# Ga_zkaUk_ad.net
KiCad netlist of a schematic drawn in EAGLE
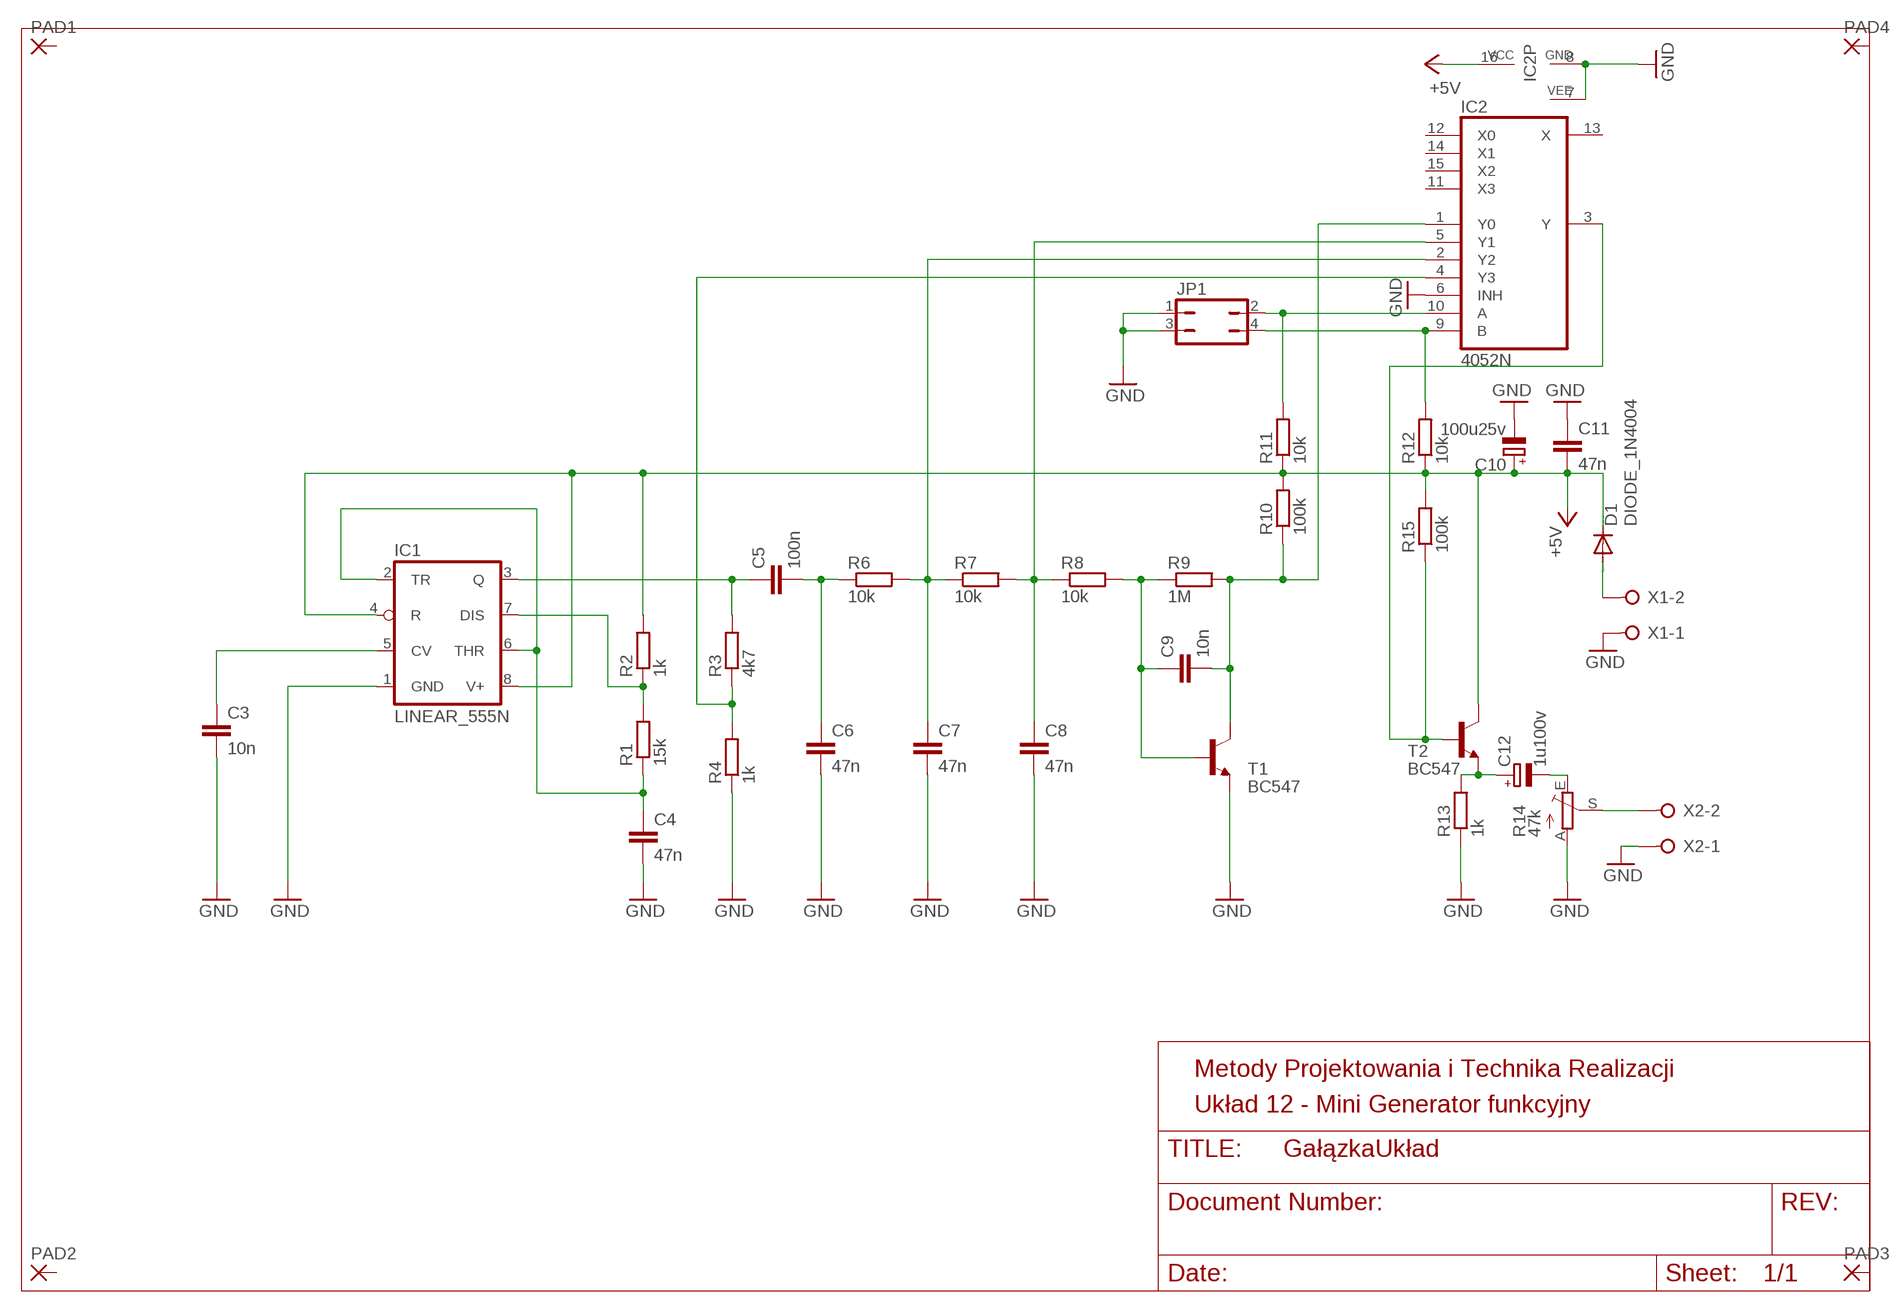
[diagram p0: schematic, sheet 1]

(export (version "E")
  (design (tool "Eeschema 10.0.6"))
  (components
    (comp (ref "C3")
      (value "10n")
      (footprint "eagle-import:C1206")
      (libsource (lib "eagle-import") (part "C-EUC1206"))
    )
    (comp (ref "C4")
      (value "47n")
      (footprint "eagle-import:C1206")
      (libsource (lib "eagle-import") (part "C-EUC1206"))
    )
    (comp (ref "C5")
      (value "100n")
      (footprint "eagle-import:C1206")
      (libsource (lib "eagle-import") (part "C-EUC1206"))
    )
    (comp (ref "C6")
      (value "47n")
      (footprint "eagle-import:C1206")
      (libsource (lib "eagle-import") (part "C-EUC1206"))
    )
    (comp (ref "C7")
      (value "47n")
      (footprint "eagle-import:C1206")
      (libsource (lib "eagle-import") (part "C-EUC1206"))
    )
    (comp (ref "C8")
      (value "47n")
      (footprint "eagle-import:C1206")
      (libsource (lib "eagle-import") (part "C-EUC1206"))
    )
    (comp (ref "C9")
      (value "10n")
      (footprint "eagle-import:C1206")
      (libsource (lib "eagle-import") (part "C-EUC1206"))
    )
    (comp (ref "C10")
      (value "100u25v")
      (footprint "eagle-import:RCL_E2,5-6")
      (libsource (lib "eagle-import") (part "RCL_CPOL-EUE2.5-6"))
    )
    (comp (ref "C11")
      (value "47n")
      (footprint "eagle-import:C1206")
      (libsource (lib "eagle-import") (part "C-EUC1206"))
    )
    (comp (ref "C12")
      (value "1u100v")
      (footprint "eagle-import:E2-5")
      (libsource (lib "eagle-import") (part "CPOL-EUE2-5"))
    )
    (comp (ref "D1")
      (value "DIODE_1N4004")
      (footprint "eagle-import:DIODE_DO41-10")
      (libsource (lib "eagle-import") (part "DIODE_1N4004"))
    )
    (comp (ref "IC1")
      (value "LINEAR_555N")
      (footprint "eagle-import:LINEAR_DIL08")
      (libsource (lib "eagle-import") (part "LINEAR_555N"))
    )
    (comp (ref "IC2")
      (value "4052N")
      (footprint "eagle-import:DIL16")
      (libsource (lib "eagle-import") (part "4052N"))
    )
    (comp (ref "JP1")
      (value "JUMPER_JP2Q")
      (footprint "eagle-import:JUMPER_JP2Q")
      (libsource (lib "eagle-import") (part "JUMPER_JP2Q"))
    )
    (comp (ref "PAD1")
      (value "2,54/1,1")
      (footprint "eagle-import:2,54_1,1")
      (libsource (lib "eagle-import") (part "2,54/1,1"))
    )
    (comp (ref "PAD2")
      (value "2,54/1,1")
      (footprint "eagle-import:2,54_1,1")
      (libsource (lib "eagle-import") (part "2,54/1,1"))
    )
    (comp (ref "PAD3")
      (value "2,54/1,1")
      (footprint "eagle-import:2,54_1,1")
      (libsource (lib "eagle-import") (part "2,54/1,1"))
    )
    (comp (ref "PAD4")
      (value "2,54/1,1")
      (footprint "eagle-import:2,54_1,1")
      (libsource (lib "eagle-import") (part "2,54/1,1"))
    )
    (comp (ref "R1")
      (value "15k")
      (footprint "eagle-import:R1206")
      (libsource (lib "eagle-import") (part "R-EU_R1206"))
    )
    (comp (ref "R2")
      (value "1k")
      (footprint "eagle-import:R1206")
      (libsource (lib "eagle-import") (part "R-EU_R1206"))
    )
    (comp (ref "R3")
      (value "4k7")
      (footprint "eagle-import:R1206")
      (libsource (lib "eagle-import") (part "R-EU_R1206"))
    )
    (comp (ref "R4")
      (value "1k")
      (footprint "eagle-import:R1206")
      (libsource (lib "eagle-import") (part "R-EU_R1206"))
    )
    (comp (ref "R6")
      (value "10k")
      (footprint "eagle-import:R1206")
      (libsource (lib "eagle-import") (part "R-EU_R1206"))
    )
    (comp (ref "R7")
      (value "10k")
      (footprint "eagle-import:R1206")
      (libsource (lib "eagle-import") (part "R-EU_R1206"))
    )
    (comp (ref "R8")
      (value "10k")
      (footprint "eagle-import:R1206")
      (libsource (lib "eagle-import") (part "R-EU_R1206"))
    )
    (comp (ref "R9")
      (value "1M")
      (footprint "eagle-import:R1206")
      (libsource (lib "eagle-import") (part "R-EU_R1206"))
    )
    (comp (ref "R10")
      (value "100k")
      (footprint "eagle-import:R1206")
      (libsource (lib "eagle-import") (part "R-EU_R1206"))
    )
    (comp (ref "R11")
      (value "10k")
      (footprint "eagle-import:R1206")
      (libsource (lib "eagle-import") (part "R-EU_R1206"))
    )
    (comp (ref "R12")
      (value "10k")
      (footprint "eagle-import:R1206")
      (libsource (lib "eagle-import") (part "R-EU_R1206"))
    )
    (comp (ref "R13")
      (value "1k")
      (footprint "eagle-import:R1206")
      (libsource (lib "eagle-import") (part "R-EU_R1206"))
    )
    (comp (ref "R14")
      (value "47k")
      (footprint "eagle-import:POT_CA6V")
      (libsource (lib "eagle-import") (part "POT_TRIM_EU-CA6V"))
    )
    (comp (ref "R15")
      (value "100k")
      (footprint "eagle-import:R1206")
      (libsource (lib "eagle-import") (part "R-EU_R1206"))
    )
    (comp (ref "T1")
      (value "BC547")
      (footprint "eagle-import:TO92")
      (libsource (lib "eagle-import") (part "BC547"))
    )
    (comp (ref "T2")
      (value "BC547")
      (footprint "eagle-import:TO92")
      (libsource (lib "eagle-import") (part "BC547"))
    )
    (comp (ref "X1")
      (value "CON-WAGO-508_W237-02P")
      (footprint "eagle-import:CON-WAGO-508_W237-132")
      (libsource (lib "eagle-import") (part "CON-WAGO-508_W237-02P"))
    )
    (comp (ref "X2")
      (value "CON-WAGO-508_W237-02P")
      (footprint "eagle-import:CON-WAGO-508_W237-132")
      (libsource (lib "eagle-import") (part "CON-WAGO-508_W237-02P"))
    )
  )
  (nets
    (net (code "1") (name "+5V") (class "Default")
      (node (ref "C10") (pin "+") (pinfunction "+_+") (pintype "passive"))
      (node (ref "C11") (pin "2") (pinfunction "2_2") (pintype "passive"))
      (node (ref "D1") (pin "C") (pinfunction "C_C") (pintype "passive"))
      (node (ref "IC1") (pin "4") (pinfunction "R_4") (pintype "input"))
      (node (ref "IC1") (pin "8") (pinfunction "V+_8") (pintype "power_in"))
      (node (ref "IC2") (pin "16") (pinfunction "VCC_16") (pintype "power_in"))
      (node (ref "R10") (pin "2") (pinfunction "2_2") (pintype "passive"))
      (node (ref "R11") (pin "1") (pinfunction "1_1") (pintype "passive"))
      (node (ref "R12") (pin "1") (pinfunction "1_1") (pintype "passive"))
      (node (ref "R15") (pin "2") (pinfunction "2_2") (pintype "passive"))
      (node (ref "R2") (pin "2") (pinfunction "2_2") (pintype "passive"))
      (node (ref "T2") (pin "3") (pinfunction "C_3") (pintype "passive"))
    )
    (net (code "2") (name "GND") (class "Default")
      (node (ref "C10") (pin "-") (pinfunction "-_-") (pintype "passive"))
      (node (ref "C11") (pin "1") (pinfunction "1_1") (pintype "passive"))
      (node (ref "C3") (pin "2") (pinfunction "2_2") (pintype "passive"))
      (node (ref "C4") (pin "2") (pinfunction "2_2") (pintype "passive"))
      (node (ref "C6") (pin "2") (pinfunction "2_2") (pintype "passive"))
      (node (ref "C7") (pin "2") (pinfunction "2_2") (pintype "passive"))
      (node (ref "C8") (pin "2") (pinfunction "2_2") (pintype "passive"))
      (node (ref "IC1") (pin "1") (pinfunction "GND_1") (pintype "power_in"))
      (node (ref "IC2") (pin "6") (pinfunction "INH_6") (pintype "input"))
      (node (ref "IC2") (pin "7") (pinfunction "VEE_7") (pintype "power_in"))
      (node (ref "IC2") (pin "8") (pinfunction "GND_8") (pintype "power_in"))
      (node (ref "JP1") (pin "1") (pinfunction "1_1") (pintype "passive"))
      (node (ref "JP1") (pin "3") (pinfunction "3_3") (pintype "passive"))
      (node (ref "R13") (pin "1") (pinfunction "1_1") (pintype "passive"))
      (node (ref "R14") (pin "A") (pinfunction "1_A") (pintype "passive"))
      (node (ref "R4") (pin "1") (pinfunction "1_1") (pintype "passive"))
      (node (ref "T1") (pin "1") (pinfunction "E_1") (pintype "passive"))
      (node (ref "X1") (pin "1") (pinfunction "KL_1") (pintype "passive"))
      (node (ref "X2") (pin "1") (pinfunction "KL_1") (pintype "passive"))
    )
    (net (code "3") (name "Net-(C5-Pad2)") (class "Default")
      (node (ref "C5") (pin "2") (pinfunction "2_2") (pintype "passive"))
      (node (ref "C6") (pin "1") (pinfunction "1_1") (pintype "passive"))
      (node (ref "R6") (pin "1") (pinfunction "1_1") (pintype "passive"))
    )
    (net (code "4") (name "Net-(IC1-CV)") (class "Default")
      (node (ref "C3") (pin "1") (pinfunction "1_1") (pintype "passive"))
      (node (ref "IC1") (pin "5") (pinfunction "CV_5") (pintype "input"))
    )
    (net (code "5") (name "Net-(IC1-DIS)") (class "Default")
      (node (ref "IC1") (pin "7") (pinfunction "DIS_7") (pintype "input"))
      (node (ref "R1") (pin "2") (pinfunction "2_2") (pintype "passive"))
      (node (ref "R2") (pin "1") (pinfunction "1_1") (pintype "passive"))
    )
    (net (code "6") (name "Net-(IC1-Q)") (class "Default")
      (node (ref "C5") (pin "1") (pinfunction "1_1") (pintype "passive"))
      (node (ref "IC1") (pin "3") (pinfunction "Q_3") (pintype "output"))
      (node (ref "R3") (pin "2") (pinfunction "2_2") (pintype "passive"))
    )
    (net (code "7") (name "Net-(IC1-THR)") (class "Default")
      (node (ref "C4") (pin "1") (pinfunction "1_1") (pintype "passive"))
      (node (ref "IC1") (pin "2") (pinfunction "TR_2") (pintype "input"))
      (node (ref "IC1") (pin "6") (pinfunction "THR_6") (pintype "input"))
      (node (ref "R1") (pin "1") (pinfunction "1_1") (pintype "passive"))
    )
    (net (code "8") (name "Net-(IC2A-A)") (class "Default")
      (node (ref "IC2") (pin "10") (pinfunction "A_10") (pintype "input"))
      (node (ref "JP1") (pin "2") (pinfunction "2_2") (pintype "passive"))
      (node (ref "R11") (pin "2") (pinfunction "2_2") (pintype "passive"))
    )
    (net (code "9") (name "Net-(IC2A-B)") (class "Default")
      (node (ref "IC2") (pin "9") (pinfunction "B_9") (pintype "input"))
      (node (ref "JP1") (pin "4") (pinfunction "4_4") (pintype "passive"))
      (node (ref "R12") (pin "2") (pinfunction "2_2") (pintype "passive"))
    )
    (net (code "10") (name "Net-(IC2A-Y)") (class "Default")
      (node (ref "IC2") (pin "3") (pinfunction "Y_3") (pintype "bidirectional"))
      (node (ref "R15") (pin "1") (pinfunction "1_1") (pintype "passive"))
      (node (ref "T2") (pin "2") (pinfunction "B_2") (pintype "passive"))
    )
    (net (code "11") (name "Net-(IC2A-Y0)") (class "Default")
      (node (ref "C9") (pin "2") (pinfunction "2_2") (pintype "passive"))
      (node (ref "IC2") (pin "1") (pinfunction "Y0_1") (pintype "bidirectional"))
      (node (ref "R10") (pin "1") (pinfunction "1_1") (pintype "passive"))
      (node (ref "R9") (pin "2") (pinfunction "2_2") (pintype "passive"))
      (node (ref "T1") (pin "3") (pinfunction "C_3") (pintype "passive"))
    )
    (net (code "12") (name "Net-(IC2A-Y1)") (class "Default")
      (node (ref "C8") (pin "1") (pinfunction "1_1") (pintype "passive"))
      (node (ref "IC2") (pin "5") (pinfunction "Y1_5") (pintype "bidirectional"))
      (node (ref "R7") (pin "2") (pinfunction "2_2") (pintype "passive"))
      (node (ref "R8") (pin "1") (pinfunction "1_1") (pintype "passive"))
    )
    (net (code "13") (name "Net-(IC2A-Y2)") (class "Default")
      (node (ref "C7") (pin "1") (pinfunction "1_1") (pintype "passive"))
      (node (ref "IC2") (pin "2") (pinfunction "Y2_2") (pintype "bidirectional"))
      (node (ref "R6") (pin "2") (pinfunction "2_2") (pintype "passive"))
      (node (ref "R7") (pin "1") (pinfunction "1_1") (pintype "passive"))
    )
    (net (code "14") (name "Net-(IC2A-Y3)") (class "Default")
      (node (ref "IC2") (pin "4") (pinfunction "Y3_4") (pintype "bidirectional"))
      (node (ref "R3") (pin "1") (pinfunction "1_1") (pintype "passive"))
      (node (ref "R4") (pin "2") (pinfunction "2_2") (pintype "passive"))
    )
    (net (code "15") (name "Net-(R14-2)") (class "Default")
      (node (ref "C12") (pin "-") (pinfunction "-_-") (pintype "passive"))
      (node (ref "R14") (pin "E") (pinfunction "2_E") (pintype "passive"))
    )
    (net (code "16") (name "Net-(R14-3)") (class "Default")
      (node (ref "R14") (pin "S") (pinfunction "3_S") (pintype "passive"))
      (node (ref "X2") (pin "2") (pinfunction "KL_2") (pintype "passive"))
    )
    (net (code "17") (name "Net-(T1-B)") (class "Default")
      (node (ref "C9") (pin "1") (pinfunction "1_1") (pintype "passive"))
      (node (ref "R8") (pin "2") (pinfunction "2_2") (pintype "passive"))
      (node (ref "R9") (pin "1") (pinfunction "1_1") (pintype "passive"))
      (node (ref "T1") (pin "2") (pinfunction "B_2") (pintype "passive"))
    )
    (net (code "18") (name "Net-(T2-E)") (class "Default")
      (node (ref "C12") (pin "+") (pinfunction "+_+") (pintype "passive"))
      (node (ref "R13") (pin "2") (pinfunction "2_2") (pintype "passive"))
      (node (ref "T2") (pin "1") (pinfunction "E_1") (pintype "passive"))
    )
    (net (code "19") (name "Net-(X1B-KL)") (class "Default")
      (node (ref "D1") (pin "A") (pinfunction "A_A") (pintype "passive"))
      (node (ref "X1") (pin "2") (pinfunction "KL_2") (pintype "passive"))
    )
    (net (code "20") (name "unconnected-(IC2A-X-Pad13)") (class "Default")
      (node (ref "IC2") (pin "13") (pinfunction "X_13") (pintype "bidirectional"))
    )
    (net (code "21") (name "unconnected-(IC2A-X0-Pad12)") (class "Default")
      (node (ref "IC2") (pin "12") (pinfunction "X0_12") (pintype "bidirectional"))
    )
    (net (code "22") (name "unconnected-(IC2A-X1-Pad14)") (class "Default")
      (node (ref "IC2") (pin "14") (pinfunction "X1_14") (pintype "bidirectional"))
    )
    (net (code "23") (name "unconnected-(IC2A-X2-Pad15)") (class "Default")
      (node (ref "IC2") (pin "15") (pinfunction "X2_15") (pintype "bidirectional"))
    )
    (net (code "24") (name "unconnected-(IC2A-X3-Pad11)") (class "Default")
      (node (ref "IC2") (pin "11") (pinfunction "X3_11") (pintype "bidirectional"))
    )
    (net (code "25") (name "unconnected-(PAD1-P-Pad1)") (class "Default")
      (node (ref "PAD1") (pin "1") (pinfunction "P_1") (pintype "passive"))
    )
    (net (code "26") (name "unconnected-(PAD2-P-Pad1)") (class "Default")
      (node (ref "PAD2") (pin "1") (pinfunction "P_1") (pintype "passive"))
    )
    (net (code "27") (name "unconnected-(PAD3-P-Pad1)") (class "Default")
      (node (ref "PAD3") (pin "1") (pinfunction "P_1") (pintype "passive"))
    )
    (net (code "28") (name "unconnected-(PAD4-P-Pad1)") (class "Default")
      (node (ref "PAD4") (pin "1") (pinfunction "P_1") (pintype "passive"))
    )
  )
)
